# circuito_centrale.net
KiCad netlist of a schematic drawn in EAGLE
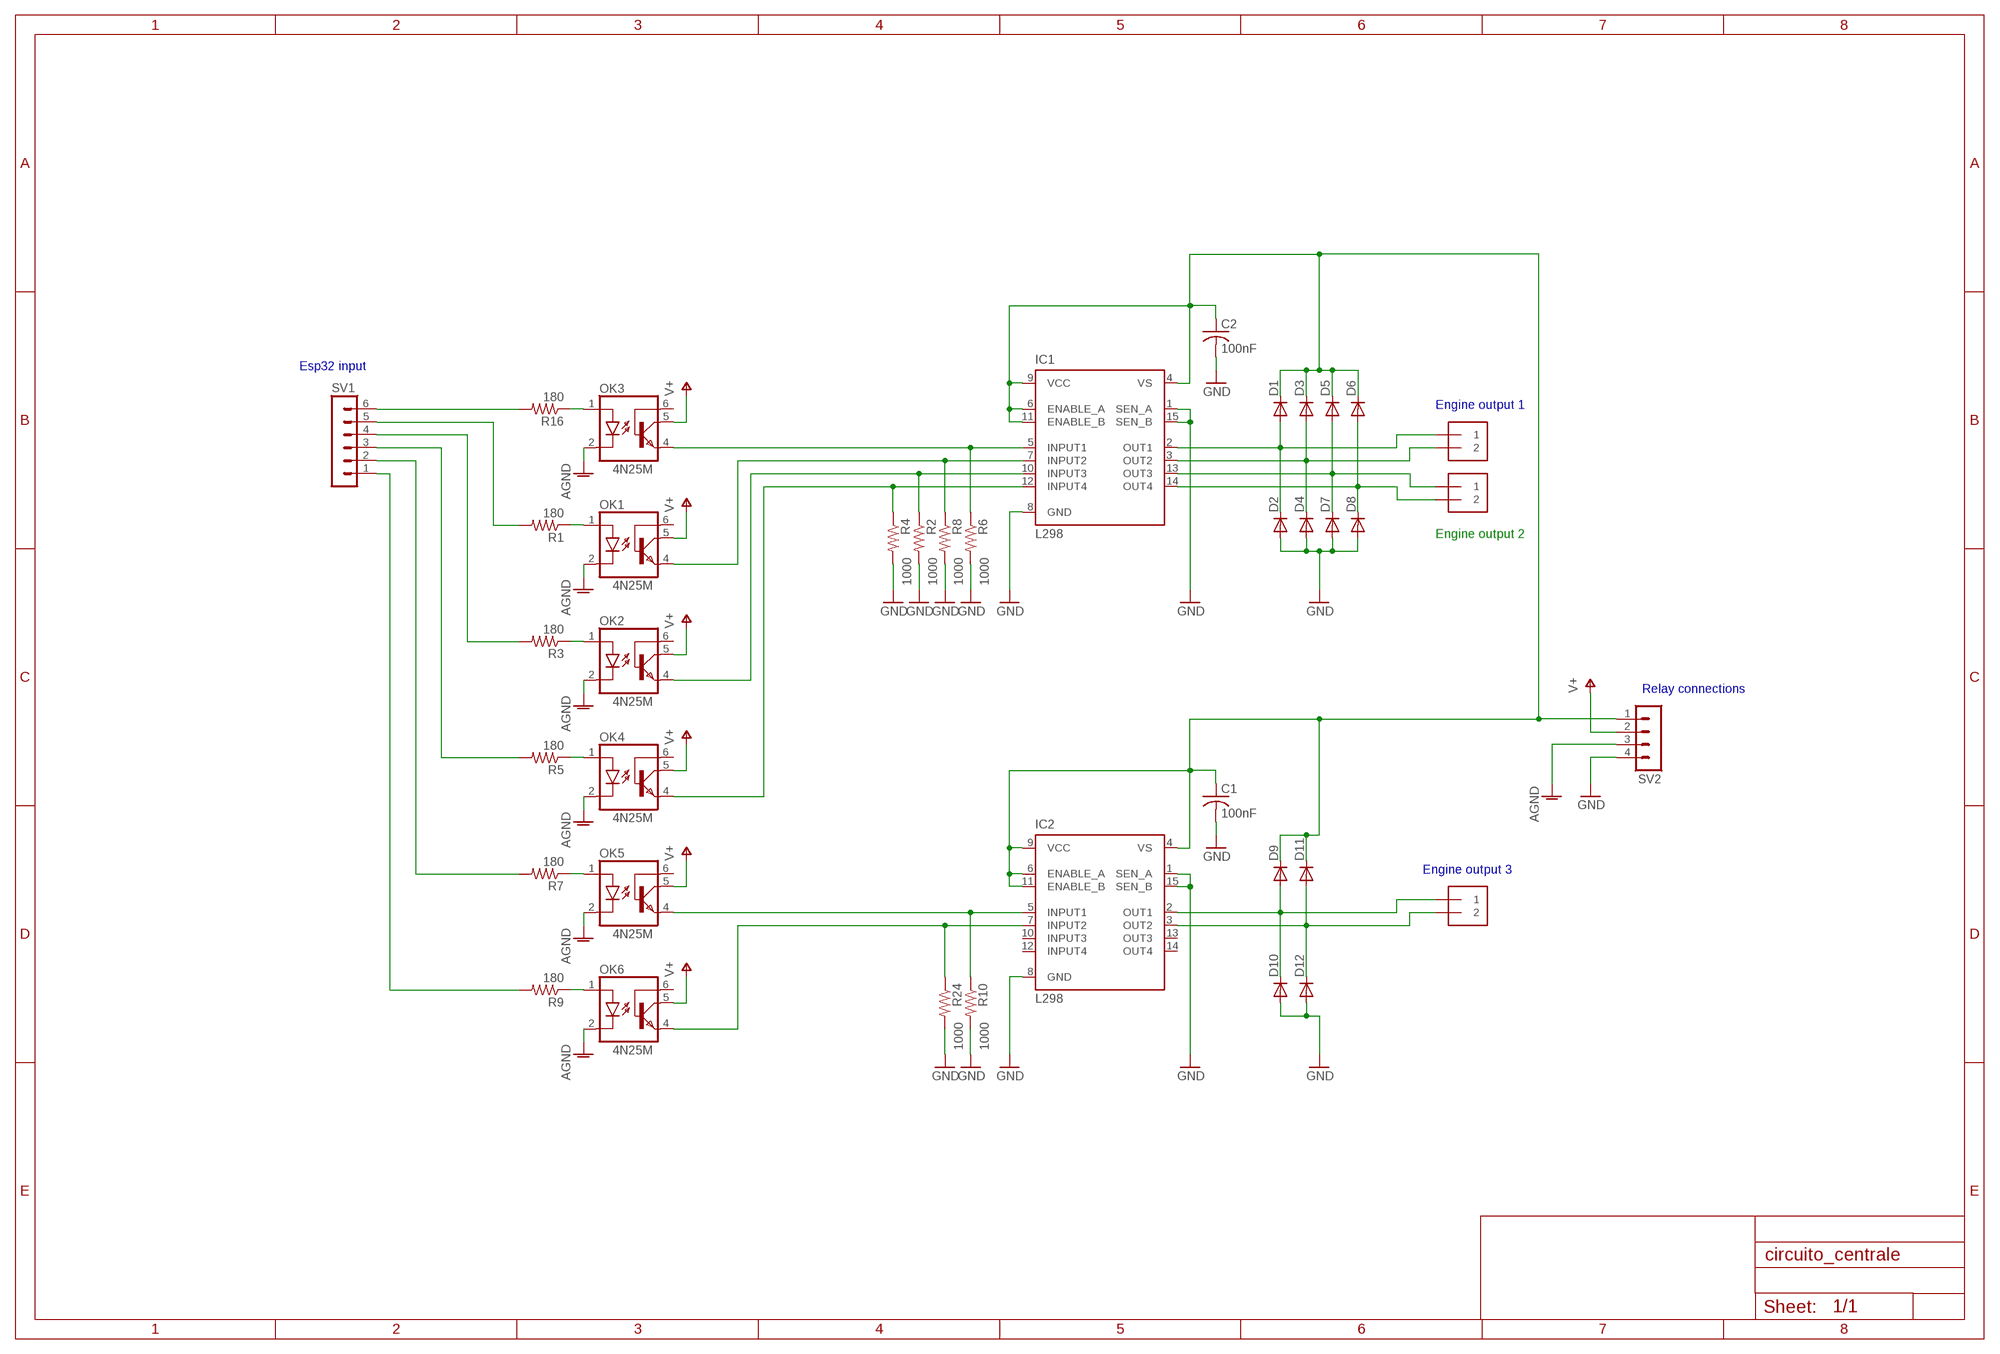
[diagram p0: schematic, sheet 1]

(export (version "E")
  (design (tool "Eeschema 10.0.6"))
  (components
    (comp (ref "C1")
      (value "100nF")
      (footprint "eagle-import:C050-024X044")
      (libsource (lib "eagle-import") (part "C-US050-024X044"))
    )
    (comp (ref "C2")
      (value "100nF")
      (footprint "eagle-import:C050-024X044")
      (libsource (lib "eagle-import") (part "C-US050-024X044"))
    )
    (comp (ref "D1")
      (value "DIODE-D-5")
      (footprint "eagle-import:D-5")
      (libsource (lib "eagle-import") (part "DIODE-D-5"))
    )
    (comp (ref "D2")
      (value "DIODE-D-5")
      (footprint "eagle-import:D-5")
      (libsource (lib "eagle-import") (part "DIODE-D-5"))
    )
    (comp (ref "D3")
      (value "DIODE-D-5")
      (footprint "eagle-import:D-5")
      (libsource (lib "eagle-import") (part "DIODE-D-5"))
    )
    (comp (ref "D4")
      (value "DIODE-D-5")
      (footprint "eagle-import:D-5")
      (libsource (lib "eagle-import") (part "DIODE-D-5"))
    )
    (comp (ref "D5")
      (value "DIODE-D-5")
      (footprint "eagle-import:D-5")
      (libsource (lib "eagle-import") (part "DIODE-D-5"))
    )
    (comp (ref "D6")
      (value "DIODE-D-5")
      (footprint "eagle-import:D-5")
      (libsource (lib "eagle-import") (part "DIODE-D-5"))
    )
    (comp (ref "D7")
      (value "DIODE-D-5")
      (footprint "eagle-import:D-5")
      (libsource (lib "eagle-import") (part "DIODE-D-5"))
    )
    (comp (ref "D8")
      (value "DIODE-D-5")
      (footprint "eagle-import:D-5")
      (libsource (lib "eagle-import") (part "DIODE-D-5"))
    )
    (comp (ref "D9")
      (value "DIODE-D-5")
      (footprint "eagle-import:D-5")
      (libsource (lib "eagle-import") (part "DIODE-D-5"))
    )
    (comp (ref "D10")
      (value "DIODE-D-5")
      (footprint "eagle-import:D-5")
      (libsource (lib "eagle-import") (part "DIODE-D-5"))
    )
    (comp (ref "D11")
      (value "DIODE-D-5")
      (footprint "eagle-import:D-5")
      (libsource (lib "eagle-import") (part "DIODE-D-5"))
    )
    (comp (ref "D12")
      (value "DIODE-D-5")
      (footprint "eagle-import:D-5")
      (libsource (lib "eagle-import") (part "DIODE-D-5"))
    )
    (comp (ref "IC1")
      (value "L298")
      (footprint "eagle-import:MULTIWATT-15")
      (fields (field (name "MPN") "L298N"))
      (libsource (lib "eagle-import") (part "L298"))
    )
    (comp (ref "IC2")
      (value "L298")
      (footprint "eagle-import:MULTIWATT-15")
      (fields (field (name "MPN") "L298N"))
      (libsource (lib "eagle-import") (part "L298"))
    )
    (comp (ref "J2")
      (value "1X2-3.5MM")
      (footprint "eagle-import:1X2-3.5MM")
      (libsource (lib "eagle-import") (part "1X2-3.5MM"))
    )
    (comp (ref "J3")
      (value "1X2-3.5MM")
      (footprint "eagle-import:1X2-3.5MM")
      (libsource (lib "eagle-import") (part "1X2-3.5MM"))
    )
    (comp (ref "J5")
      (value "1X2-3.5MM")
      (footprint "eagle-import:1X2-3.5MM")
      (libsource (lib "eagle-import") (part "1X2-3.5MM"))
    )
    (comp (ref "OK1")
      (value "4N25M")
      (footprint "eagle-import:DIL06")
      (fields (field (name "MPN") "4N25-M"))
      (libsource (lib "eagle-import") (part "4N?M25"))
    )
    (comp (ref "OK2")
      (value "4N25M")
      (footprint "eagle-import:DIL06")
      (fields (field (name "MPN") "4N25-M"))
      (libsource (lib "eagle-import") (part "4N?M25"))
    )
    (comp (ref "OK3")
      (value "4N25M")
      (footprint "eagle-import:DIL06")
      (fields (field (name "MPN") "4N25-M"))
      (libsource (lib "eagle-import") (part "4N?M25"))
    )
    (comp (ref "OK4")
      (value "4N25M")
      (footprint "eagle-import:DIL06")
      (fields (field (name "MPN") "4N25-M"))
      (libsource (lib "eagle-import") (part "4N?M25"))
    )
    (comp (ref "OK5")
      (value "4N25M")
      (footprint "eagle-import:DIL06")
      (fields (field (name "MPN") "4N25-M"))
      (libsource (lib "eagle-import") (part "4N?M25"))
    )
    (comp (ref "OK6")
      (value "4N25M")
      (footprint "eagle-import:DIL06")
      (fields (field (name "MPN") "4N25-M"))
      (libsource (lib "eagle-import") (part "4N?M25"))
    )
    (comp (ref "R1")
      (value "180")
      (footprint "eagle-import:0207_10")
      (libsource (lib "eagle-import") (part "R-US_0207/10"))
    )
    (comp (ref "R2")
      (value "1000")
      (footprint "eagle-import:0207_10")
      (libsource (lib "eagle-import") (part "R-US_0207/10"))
    )
    (comp (ref "R3")
      (value "180")
      (footprint "eagle-import:0207_10")
      (libsource (lib "eagle-import") (part "R-US_0207/10"))
    )
    (comp (ref "R4")
      (value "1000")
      (footprint "eagle-import:0207_10")
      (libsource (lib "eagle-import") (part "R-US_0207/10"))
    )
    (comp (ref "R5")
      (value "180")
      (footprint "eagle-import:0207_10")
      (libsource (lib "eagle-import") (part "R-US_0207/10"))
    )
    (comp (ref "R6")
      (value "1000")
      (footprint "eagle-import:0207_10")
      (libsource (lib "eagle-import") (part "R-US_0207/10"))
    )
    (comp (ref "R7")
      (value "180")
      (footprint "eagle-import:0207_10")
      (libsource (lib "eagle-import") (part "R-US_0207/10"))
    )
    (comp (ref "R8")
      (value "1000")
      (footprint "eagle-import:0207_10")
      (libsource (lib "eagle-import") (part "R-US_0207/10"))
    )
    (comp (ref "R9")
      (value "180")
      (footprint "eagle-import:0207_10")
      (libsource (lib "eagle-import") (part "R-US_0207/10"))
    )
    (comp (ref "R10")
      (value "1000")
      (footprint "eagle-import:0207_10")
      (libsource (lib "eagle-import") (part "R-US_0207/10"))
    )
    (comp (ref "R16")
      (value "180")
      (footprint "eagle-import:0207_10")
      (libsource (lib "eagle-import") (part "R-US_0207/10"))
    )
    (comp (ref "R24")
      (value "1000")
      (footprint "eagle-import:0207_10")
      (libsource (lib "eagle-import") (part "R-US_0207/10"))
    )
    (comp (ref "SV1")
      (value "MA06-1")
      (footprint "eagle-import:MA06-1")
      (libsource (lib "eagle-import") (part "MA06-1"))
    )
    (comp (ref "SV2")
      (value "MA04-1")
      (footprint "eagle-import:MA04-1")
      (libsource (lib "eagle-import") (part "MA04-1"))
    )
  )
  (nets
    (net (code "1") (name "AGND") (class "Default")
      (node (ref "OK1") (pin "2") (pinfunction "C_2") (pintype "passive"))
      (node (ref "OK2") (pin "2") (pinfunction "C_2") (pintype "passive"))
      (node (ref "OK3") (pin "2") (pinfunction "C_2") (pintype "passive"))
      (node (ref "OK4") (pin "2") (pinfunction "C_2") (pintype "passive"))
      (node (ref "OK5") (pin "2") (pinfunction "C_2") (pintype "passive"))
      (node (ref "OK6") (pin "2") (pinfunction "C_2") (pintype "passive"))
      (node (ref "SV2") (pin "3") (pinfunction "3_3") (pintype "passive"))
    )
    (net (code "2") (name "GND") (class "Default")
      (node (ref "C1") (pin "2") (pinfunction "2_2") (pintype "passive"))
      (node (ref "C2") (pin "2") (pinfunction "2_2") (pintype "passive"))
      (node (ref "D10") (pin "A") (pinfunction "A_A") (pintype "passive"))
      (node (ref "D12") (pin "A") (pinfunction "A_A") (pintype "passive"))
      (node (ref "D2") (pin "A") (pinfunction "A_A") (pintype "passive"))
      (node (ref "D4") (pin "A") (pinfunction "A_A") (pintype "passive"))
      (node (ref "D7") (pin "A") (pinfunction "A_A") (pintype "passive"))
      (node (ref "D8") (pin "A") (pinfunction "A_A") (pintype "passive"))
      (node (ref "IC1") (pin "1") (pinfunction "SEN_A_1") (pintype "input"))
      (node (ref "IC1") (pin "15") (pinfunction "SEN_B_15") (pintype "input"))
      (node (ref "IC1") (pin "8") (pinfunction "GND_8") (pintype "power_in"))
      (node (ref "IC2") (pin "1") (pinfunction "SEN_A_1") (pintype "input"))
      (node (ref "IC2") (pin "15") (pinfunction "SEN_B_15") (pintype "input"))
      (node (ref "IC2") (pin "8") (pinfunction "GND_8") (pintype "power_in"))
      (node (ref "R10") (pin "2") (pinfunction "2_2") (pintype "passive"))
      (node (ref "R2") (pin "2") (pinfunction "2_2") (pintype "passive"))
      (node (ref "R24") (pin "2") (pinfunction "2_2") (pintype "passive"))
      (node (ref "R4") (pin "2") (pinfunction "2_2") (pintype "passive"))
      (node (ref "R6") (pin "2") (pinfunction "2_2") (pintype "passive"))
      (node (ref "R8") (pin "2") (pinfunction "2_2") (pintype "passive"))
      (node (ref "SV2") (pin "4") (pinfunction "4_4") (pintype "passive"))
    )
    (net (code "3") (name "Net-(IC1-ENABLE_A)") (class "Default")
      (node (ref "C1") (pin "1") (pinfunction "1_1") (pintype "passive"))
      (node (ref "C2") (pin "1") (pinfunction "1_1") (pintype "passive"))
      (node (ref "D1") (pin "C") (pinfunction "C_C") (pintype "passive"))
      (node (ref "D11") (pin "C") (pinfunction "C_C") (pintype "passive"))
      (node (ref "D3") (pin "C") (pinfunction "C_C") (pintype "passive"))
      (node (ref "D5") (pin "C") (pinfunction "C_C") (pintype "passive"))
      (node (ref "D6") (pin "C") (pinfunction "C_C") (pintype "passive"))
      (node (ref "D9") (pin "C") (pinfunction "C_C") (pintype "passive"))
      (node (ref "IC1") (pin "11") (pinfunction "ENABLE_B_11") (pintype "input"))
      (node (ref "IC1") (pin "4") (pinfunction "VS_4") (pintype "power_in"))
      (node (ref "IC1") (pin "6") (pinfunction "ENABLE_A_6") (pintype "input"))
      (node (ref "IC1") (pin "9") (pinfunction "VCC_9") (pintype "power_in"))
      (node (ref "IC2") (pin "11") (pinfunction "ENABLE_B_11") (pintype "input"))
      (node (ref "IC2") (pin "4") (pinfunction "VS_4") (pintype "power_in"))
      (node (ref "IC2") (pin "6") (pinfunction "ENABLE_A_6") (pintype "input"))
      (node (ref "IC2") (pin "9") (pinfunction "VCC_9") (pintype "power_in"))
      (node (ref "SV2") (pin "1") (pinfunction "1_1") (pintype "passive"))
    )
    (net (code "4") (name "Net-(IC1-INPUT1)") (class "Default")
      (node (ref "IC1") (pin "5") (pinfunction "INPUT1_5") (pintype "input"))
      (node (ref "OK3") (pin "4") (pinfunction "EMI_4") (pintype "passive"))
      (node (ref "R6") (pin "1") (pinfunction "1_1") (pintype "passive"))
    )
    (net (code "5") (name "Net-(IC1-INPUT2)") (class "Default")
      (node (ref "IC1") (pin "7") (pinfunction "INPUT2_7") (pintype "input"))
      (node (ref "OK1") (pin "4") (pinfunction "EMI_4") (pintype "passive"))
      (node (ref "R8") (pin "1") (pinfunction "1_1") (pintype "passive"))
    )
    (net (code "6") (name "Net-(IC1-INPUT3)") (class "Default")
      (node (ref "IC1") (pin "10") (pinfunction "INPUT3_10") (pintype "input"))
      (node (ref "OK2") (pin "4") (pinfunction "EMI_4") (pintype "passive"))
      (node (ref "R2") (pin "1") (pinfunction "1_1") (pintype "passive"))
    )
    (net (code "7") (name "Net-(IC1-INPUT4)") (class "Default")
      (node (ref "IC1") (pin "12") (pinfunction "INPUT4_12") (pintype "input"))
      (node (ref "OK4") (pin "4") (pinfunction "EMI_4") (pintype "passive"))
      (node (ref "R4") (pin "1") (pinfunction "1_1") (pintype "passive"))
    )
    (net (code "8") (name "Net-(IC1-OUT1)") (class "Default")
      (node (ref "D1") (pin "A") (pinfunction "A_A") (pintype "passive"))
      (node (ref "D2") (pin "C") (pinfunction "C_C") (pintype "passive"))
      (node (ref "IC1") (pin "2") (pinfunction "OUT1_2") (pintype "output"))
      (node (ref "J2") (pin "1") (pinfunction "1_1") (pintype "passive"))
    )
    (net (code "9") (name "Net-(IC1-OUT2)") (class "Default")
      (node (ref "D3") (pin "A") (pinfunction "A_A") (pintype "passive"))
      (node (ref "D4") (pin "C") (pinfunction "C_C") (pintype "passive"))
      (node (ref "IC1") (pin "3") (pinfunction "OUT2_3") (pintype "output"))
      (node (ref "J2") (pin "2") (pinfunction "2_2") (pintype "passive"))
    )
    (net (code "10") (name "Net-(IC1-OUT3)") (class "Default")
      (node (ref "D5") (pin "A") (pinfunction "A_A") (pintype "passive"))
      (node (ref "D7") (pin "C") (pinfunction "C_C") (pintype "passive"))
      (node (ref "IC1") (pin "13") (pinfunction "OUT3_13") (pintype "output"))
      (node (ref "J3") (pin "1") (pinfunction "1_1") (pintype "passive"))
    )
    (net (code "11") (name "Net-(IC1-OUT4)") (class "Default")
      (node (ref "D6") (pin "A") (pinfunction "A_A") (pintype "passive"))
      (node (ref "D8") (pin "C") (pinfunction "C_C") (pintype "passive"))
      (node (ref "IC1") (pin "14") (pinfunction "OUT4_14") (pintype "output"))
      (node (ref "J3") (pin "2") (pinfunction "2_2") (pintype "passive"))
    )
    (net (code "12") (name "Net-(IC2-INPUT1)") (class "Default")
      (node (ref "IC2") (pin "5") (pinfunction "INPUT1_5") (pintype "input"))
      (node (ref "OK5") (pin "4") (pinfunction "EMI_4") (pintype "passive"))
      (node (ref "R10") (pin "1") (pinfunction "1_1") (pintype "passive"))
    )
    (net (code "13") (name "Net-(IC2-INPUT2)") (class "Default")
      (node (ref "IC2") (pin "7") (pinfunction "INPUT2_7") (pintype "input"))
      (node (ref "OK6") (pin "4") (pinfunction "EMI_4") (pintype "passive"))
      (node (ref "R24") (pin "1") (pinfunction "1_1") (pintype "passive"))
    )
    (net (code "14") (name "Net-(IC2-OUT1)") (class "Default")
      (node (ref "D10") (pin "C") (pinfunction "C_C") (pintype "passive"))
      (node (ref "D9") (pin "A") (pinfunction "A_A") (pintype "passive"))
      (node (ref "IC2") (pin "2") (pinfunction "OUT1_2") (pintype "output"))
      (node (ref "J5") (pin "1") (pinfunction "1_1") (pintype "passive"))
    )
    (net (code "15") (name "Net-(IC2-OUT2)") (class "Default")
      (node (ref "D11") (pin "A") (pinfunction "A_A") (pintype "passive"))
      (node (ref "D12") (pin "C") (pinfunction "C_C") (pintype "passive"))
      (node (ref "IC2") (pin "3") (pinfunction "OUT2_3") (pintype "output"))
      (node (ref "J5") (pin "2") (pinfunction "2_2") (pintype "passive"))
    )
    (net (code "16") (name "Net-(OK1-A)") (class "Default")
      (node (ref "OK1") (pin "1") (pinfunction "A_1") (pintype "passive"))
      (node (ref "R1") (pin "1") (pinfunction "1_1") (pintype "passive"))
    )
    (net (code "17") (name "Net-(OK2-A)") (class "Default")
      (node (ref "OK2") (pin "1") (pinfunction "A_1") (pintype "passive"))
      (node (ref "R3") (pin "1") (pinfunction "1_1") (pintype "passive"))
    )
    (net (code "18") (name "Net-(OK3-A)") (class "Default")
      (node (ref "OK3") (pin "1") (pinfunction "A_1") (pintype "passive"))
      (node (ref "R16") (pin "1") (pinfunction "1_1") (pintype "passive"))
    )
    (net (code "19") (name "Net-(OK4-A)") (class "Default")
      (node (ref "OK4") (pin "1") (pinfunction "A_1") (pintype "passive"))
      (node (ref "R5") (pin "1") (pinfunction "1_1") (pintype "passive"))
    )
    (net (code "20") (name "Net-(OK5-A)") (class "Default")
      (node (ref "OK5") (pin "1") (pinfunction "A_1") (pintype "passive"))
      (node (ref "R7") (pin "1") (pinfunction "1_1") (pintype "passive"))
    )
    (net (code "21") (name "Net-(OK6-A)") (class "Default")
      (node (ref "OK6") (pin "1") (pinfunction "A_1") (pintype "passive"))
      (node (ref "R9") (pin "1") (pinfunction "1_1") (pintype "passive"))
    )
    (net (code "22") (name "Net-(R1-Pad2)") (class "Default")
      (node (ref "R1") (pin "2") (pinfunction "2_2") (pintype "passive"))
      (node (ref "SV1") (pin "5") (pinfunction "5_5") (pintype "passive"))
    )
    (net (code "23") (name "Net-(R3-Pad2)") (class "Default")
      (node (ref "R3") (pin "2") (pinfunction "2_2") (pintype "passive"))
      (node (ref "SV1") (pin "4") (pinfunction "4_4") (pintype "passive"))
    )
    (net (code "24") (name "Net-(R5-Pad2)") (class "Default")
      (node (ref "R5") (pin "2") (pinfunction "2_2") (pintype "passive"))
      (node (ref "SV1") (pin "3") (pinfunction "3_3") (pintype "passive"))
    )
    (net (code "25") (name "Net-(R7-Pad2)") (class "Default")
      (node (ref "R7") (pin "2") (pinfunction "2_2") (pintype "passive"))
      (node (ref "SV1") (pin "2") (pinfunction "2_2") (pintype "passive"))
    )
    (net (code "26") (name "Net-(R9-Pad2)") (class "Default")
      (node (ref "R9") (pin "2") (pinfunction "2_2") (pintype "passive"))
      (node (ref "SV1") (pin "1") (pinfunction "1_1") (pintype "passive"))
    )
    (net (code "27") (name "Net-(R16-Pad2)") (class "Default")
      (node (ref "R16") (pin "2") (pinfunction "2_2") (pintype "passive"))
      (node (ref "SV1") (pin "6") (pinfunction "6_6") (pintype "passive"))
    )
    (net (code "28") (name "V+") (class "Default")
      (node (ref "OK1") (pin "5") (pinfunction "COL_5") (pintype "passive"))
      (node (ref "OK2") (pin "5") (pinfunction "COL_5") (pintype "passive"))
      (node (ref "OK3") (pin "5") (pinfunction "COL_5") (pintype "passive"))
      (node (ref "OK4") (pin "5") (pinfunction "COL_5") (pintype "passive"))
      (node (ref "OK5") (pin "5") (pinfunction "COL_5") (pintype "passive"))
      (node (ref "OK6") (pin "5") (pinfunction "COL_5") (pintype "passive"))
      (node (ref "SV2") (pin "2") (pinfunction "2_2") (pintype "passive"))
    )
    (net (code "29") (name "unconnected-(IC2-INPUT3-Pad10)") (class "Default")
      (node (ref "IC2") (pin "10") (pinfunction "INPUT3_10") (pintype "input"))
    )
    (net (code "30") (name "unconnected-(IC2-INPUT4-Pad12)") (class "Default")
      (node (ref "IC2") (pin "12") (pinfunction "INPUT4_12") (pintype "input"))
    )
    (net (code "31") (name "unconnected-(IC2-OUT3-Pad13)") (class "Default")
      (node (ref "IC2") (pin "13") (pinfunction "OUT3_13") (pintype "output"))
    )
    (net (code "32") (name "unconnected-(IC2-OUT4-Pad14)") (class "Default")
      (node (ref "IC2") (pin "14") (pinfunction "OUT4_14") (pintype "output"))
    )
    (net (code "33") (name "unconnected-(OK1-BAS-Pad6)") (class "Default")
      (node (ref "OK1") (pin "6") (pinfunction "BAS_6") (pintype "passive"))
    )
    (net (code "34") (name "unconnected-(OK2-BAS-Pad6)") (class "Default")
      (node (ref "OK2") (pin "6") (pinfunction "BAS_6") (pintype "passive"))
    )
    (net (code "35") (name "unconnected-(OK3-BAS-Pad6)") (class "Default")
      (node (ref "OK3") (pin "6") (pinfunction "BAS_6") (pintype "passive"))
    )
    (net (code "36") (name "unconnected-(OK4-BAS-Pad6)") (class "Default")
      (node (ref "OK4") (pin "6") (pinfunction "BAS_6") (pintype "passive"))
    )
    (net (code "37") (name "unconnected-(OK5-BAS-Pad6)") (class "Default")
      (node (ref "OK5") (pin "6") (pinfunction "BAS_6") (pintype "passive"))
    )
    (net (code "38") (name "unconnected-(OK6-BAS-Pad6)") (class "Default")
      (node (ref "OK6") (pin "6") (pinfunction "BAS_6") (pintype "passive"))
    )
  )
)
